# sensor_garis.net
KiCad netlist of a schematic drawn in EAGLE
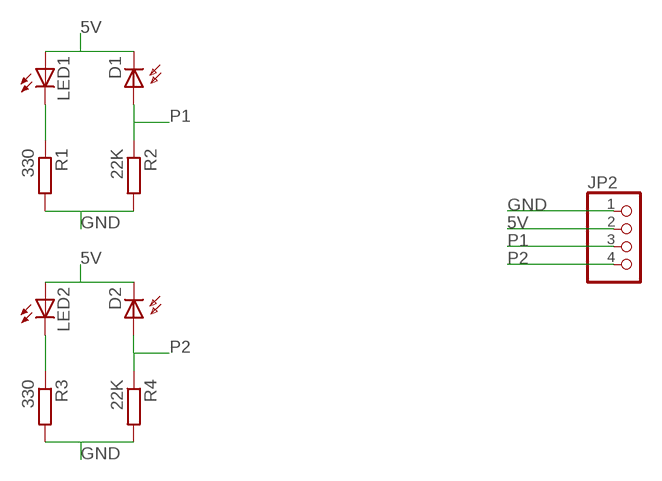
[diagram p0: schematic, sheet 1]

(export (version "E")
  (design (tool "Eeschema 10.0.6"))
  (components
    (comp (ref "D1")
      (value "BPX65")
      (footprint "eagle-import:BPX65")
      (fields (field (name "MPN") "BPX65."))
      (libsource (lib "eagle-import") (part "BPX65"))
    )
    (comp (ref "D2")
      (value "BPX65")
      (footprint "eagle-import:BPX65")
      (fields (field (name "MPN") "BPX65."))
      (libsource (lib "eagle-import") (part "BPX65"))
    )
    (comp (ref "JP2")
      (value "PINHD-1X4")
      (footprint "eagle-import:1X04")
      (libsource (lib "eagle-import") (part "PINHD-1X4"))
    )
    (comp (ref "LED1")
      (value "LED3MM")
      (footprint "eagle-import:LED3MM")
      (libsource (lib "eagle-import") (part "LED3MM"))
    )
    (comp (ref "LED2")
      (value "LED3MM")
      (footprint "eagle-import:LED3MM")
      (libsource (lib "eagle-import") (part "LED3MM"))
    )
    (comp (ref "R1")
      (value "330")
      (footprint "eagle-import:0207_7")
      (libsource (lib "eagle-import") (part "R-EU_0207/7"))
    )
    (comp (ref "R2")
      (value "22K")
      (footprint "eagle-import:0207_7")
      (libsource (lib "eagle-import") (part "R-EU_0207/7"))
    )
    (comp (ref "R3")
      (value "330")
      (footprint "eagle-import:0207_7")
      (libsource (lib "eagle-import") (part "R-EU_0207/7"))
    )
    (comp (ref "R4")
      (value "22K")
      (footprint "eagle-import:0207_7")
      (libsource (lib "eagle-import") (part "R-EU_0207/7"))
    )
  )
  (nets
    (net (code "1") (name "/5V") (class "Default")
      (node (ref "D1") (pin "K") (pinfunction "C_K") (pintype "passive"))
      (node (ref "D2") (pin "K") (pinfunction "C_K") (pintype "passive"))
      (node (ref "JP2") (pin "2") (pinfunction "2_2") (pintype "passive"))
      (node (ref "LED1") (pin "A") (pinfunction "A_A") (pintype "passive"))
      (node (ref "LED2") (pin "A") (pinfunction "A_A") (pintype "passive"))
    )
    (net (code "2") (name "/GND") (class "Default")
      (node (ref "JP2") (pin "1") (pinfunction "1_1") (pintype "passive"))
      (node (ref "R1") (pin "2") (pinfunction "2_2") (pintype "passive"))
      (node (ref "R2") (pin "2") (pinfunction "2_2") (pintype "passive"))
      (node (ref "R3") (pin "2") (pinfunction "2_2") (pintype "passive"))
      (node (ref "R4") (pin "2") (pinfunction "2_2") (pintype "passive"))
    )
    (net (code "3") (name "/P1") (class "Default")
      (node (ref "D1") (pin "A") (pinfunction "A_A") (pintype "passive"))
      (node (ref "JP2") (pin "3") (pinfunction "3_3") (pintype "passive"))
      (node (ref "R2") (pin "1") (pinfunction "1_1") (pintype "passive"))
    )
    (net (code "4") (name "/P2") (class "Default")
      (node (ref "D2") (pin "A") (pinfunction "A_A") (pintype "passive"))
      (node (ref "JP2") (pin "4") (pinfunction "4_4") (pintype "passive"))
      (node (ref "R4") (pin "1") (pinfunction "1_1") (pintype "passive"))
    )
    (net (code "5") (name "Net-(LED1-C)") (class "Default")
      (node (ref "LED1") (pin "K") (pinfunction "C_K") (pintype "passive"))
      (node (ref "R1") (pin "1") (pinfunction "1_1") (pintype "passive"))
    )
    (net (code "6") (name "Net-(LED2-C)") (class "Default")
      (node (ref "LED2") (pin "K") (pinfunction "C_K") (pintype "passive"))
      (node (ref "R3") (pin "1") (pinfunction "1_1") (pintype "passive"))
    )
  )
)
